# Power_P2V5.net
KiCad netlist of a schematic drawn in Altium Designer
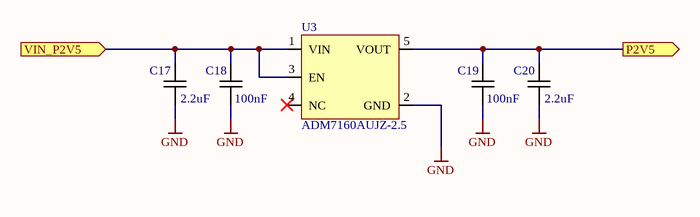
[diagram p0: Power_P2V5.SchDoc]

(export (version "E")
  (design (tool "Eeschema 10.0.6"))
  (components
    (comp (ref "C17")
      (value "2.2uF")
      (footprint "CAPC0603X90N")
      (description "Non-polarised capacitor")
      (fields (field (name "MANUFACTURER PART NUMBER") "GRM188Z71C225KE43D"))
      (libsource (lib "Capacitors") (part "Capacitor - non polarized"))
    )
    (comp (ref "C18")
      (value "100nF")
      (footprint "CAPC0603X90N")
      (description "Non-polarised capacitor")
      (fields (field (name "MANUFACTURER PART NUMBER") "VJ0603Y104KXJCW1BC"))
      (libsource (lib "Capacitors") (part "Capacitor - non polarized"))
    )
    (comp (ref "C19")
      (value "100nF")
      (footprint "CAPC0603X90N")
      (description "Non-polarised capacitor")
      (fields (field (name "MANUFACTURER PART NUMBER") "VJ0603Y104KXJCW1BC"))
      (libsource (lib "Capacitors") (part "Capacitor - non polarized"))
    )
    (comp (ref "C20")
      (value "2.2uF")
      (footprint "CAPC0603X90N")
      (description "Non-polarised capacitor")
      (fields (field (name "MANUFACTURER PART NUMBER") "GRM188Z71C225KE43D"))
      (libsource (lib "Capacitors") (part "Capacitor - non polarized"))
    )
    (comp (ref "U3")
      (value "ADM7160AUJZ-2.5")
      (description "Ultralow Noise, 200 mA Linear Regulator, 2.5V out")
      (libsource (lib "ICs_and_Semiconductors") (part "ADM7160AUJZ"))
    )
  )
  (nets
    (net (code "1") (name "/P2V5") (class "Default")
      (node (ref "C19") (pin "1") (pinfunction "1_1") (pintype "passive"))
      (node (ref "C20") (pin "1") (pinfunction "1_1") (pintype "passive"))
      (node (ref "U3") (pin "5") (pinfunction "VOUT_5") (pintype "power_in"))
    )
    (net (code "2") (name "/VIN_P2V5") (class "Default")
      (node (ref "C17") (pin "1") (pinfunction "1_1") (pintype "passive"))
      (node (ref "C18") (pin "1") (pinfunction "1_1") (pintype "passive"))
      (node (ref "U3") (pin "1") (pinfunction "VIN_1") (pintype "power_in"))
      (node (ref "U3") (pin "3") (pinfunction "EN_3") (pintype "passive"))
    )
    (net (code "3") (name "GND") (class "Default")
      (node (ref "C17") (pin "2") (pinfunction "2_2") (pintype "passive"))
      (node (ref "C18") (pin "2") (pinfunction "2_2") (pintype "passive"))
      (node (ref "C19") (pin "2") (pinfunction "2_2") (pintype "passive"))
      (node (ref "C20") (pin "2") (pinfunction "2_2") (pintype "passive"))
      (node (ref "U3") (pin "2") (pinfunction "GND_2") (pintype "power_in"))
    )
    (net (code "4") (name "unconnected-(U3-NC-Pad4)") (class "Default")
      (node (ref "U3") (pin "4") (pinfunction "NC_4") (pintype "passive+no_connect"))
    )
  )
)
